# Sheet2.net
KiCad netlist of a schematic drawn in Altium Designer
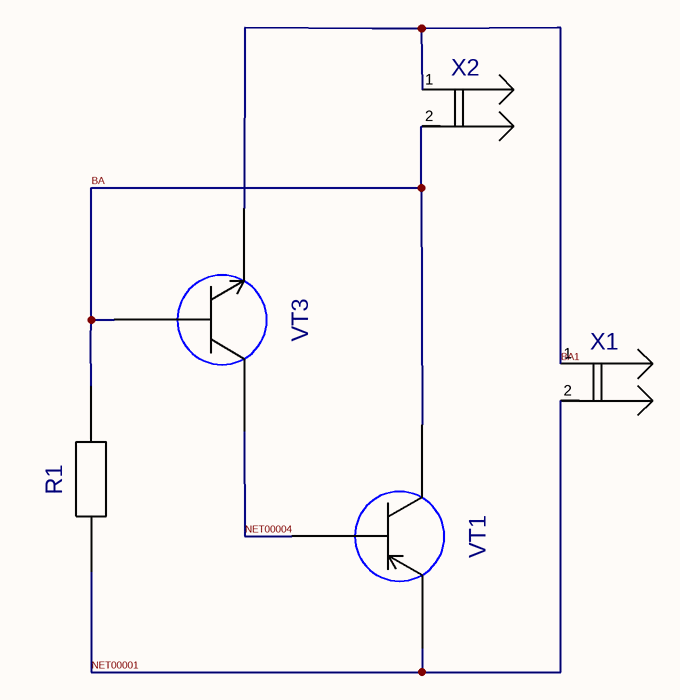
[diagram p0: Sheet2.SCHDOC]

(export (version "E")
  (design (tool "Eeschema 10.0.6"))
  (components
    (comp (ref "R1") (value "MURATA MF12") (footprint "RES400") (libsource (lib "*") (part "MURATA MF12")))
    (comp (ref "VT1") (value "КТ361") (footprint "КТ315") (libsource (lib "*") (part "КТ361")))
    (comp (ref "VT3") (value "КТ815") (footprint "КТ815") (libsource (lib "*") (part "КТ815")))
    (comp (ref "X1") (value "2XR") (footprint "2XR") (libsource (lib "*") (part "2XR")))
    (comp (ref "X2") (value "2XR") (footprint "2XR") (libsource (lib "*") (part "2XR")))
  )
  (nets
    (net (code "1") (name "/BA") (class "Default")
      (node (ref "R1") (pin "2") (pinfunction "A2_2") (pintype "passive"))
      (node (ref "VT1") (pin "2") (pinfunction "A2_2") (pintype "passive"))
      (node (ref "VT3") (pin "1") (pinfunction "A1_1") (pintype "passive"))
      (node (ref "X2") (pin "2") (pinfunction "I/O2_2") (pintype "passive"))
    )
    (net (code "2") (name "/BA1") (class "Default")
      (node (ref "VT3") (pin "3") (pinfunction "A3_3") (pintype "passive"))
      (node (ref "X1") (pin "1") (pinfunction "I/O1_1") (pintype "passive"))
      (node (ref "X2") (pin "1") (pinfunction "I/O1_1") (pintype "passive"))
    )
    (net (code "3") (name "/NET00001") (class "Default")
      (node (ref "R1") (pin "1") (pinfunction "A1_1") (pintype "passive"))
      (node (ref "VT1") (pin "3") (pinfunction "A3_3") (pintype "passive"))
      (node (ref "X1") (pin "2") (pinfunction "I/O2_2") (pintype "passive"))
    )
    (net (code "4") (name "/NET00004") (class "Default")
      (node (ref "VT1") (pin "1") (pinfunction "A1_1") (pintype "passive"))
      (node (ref "VT3") (pin "2") (pinfunction "A2_2") (pintype "passive"))
    )
  )
)
